# testscreen_4x4.net
KiCad netlist of a schematic drawn in EAGLE
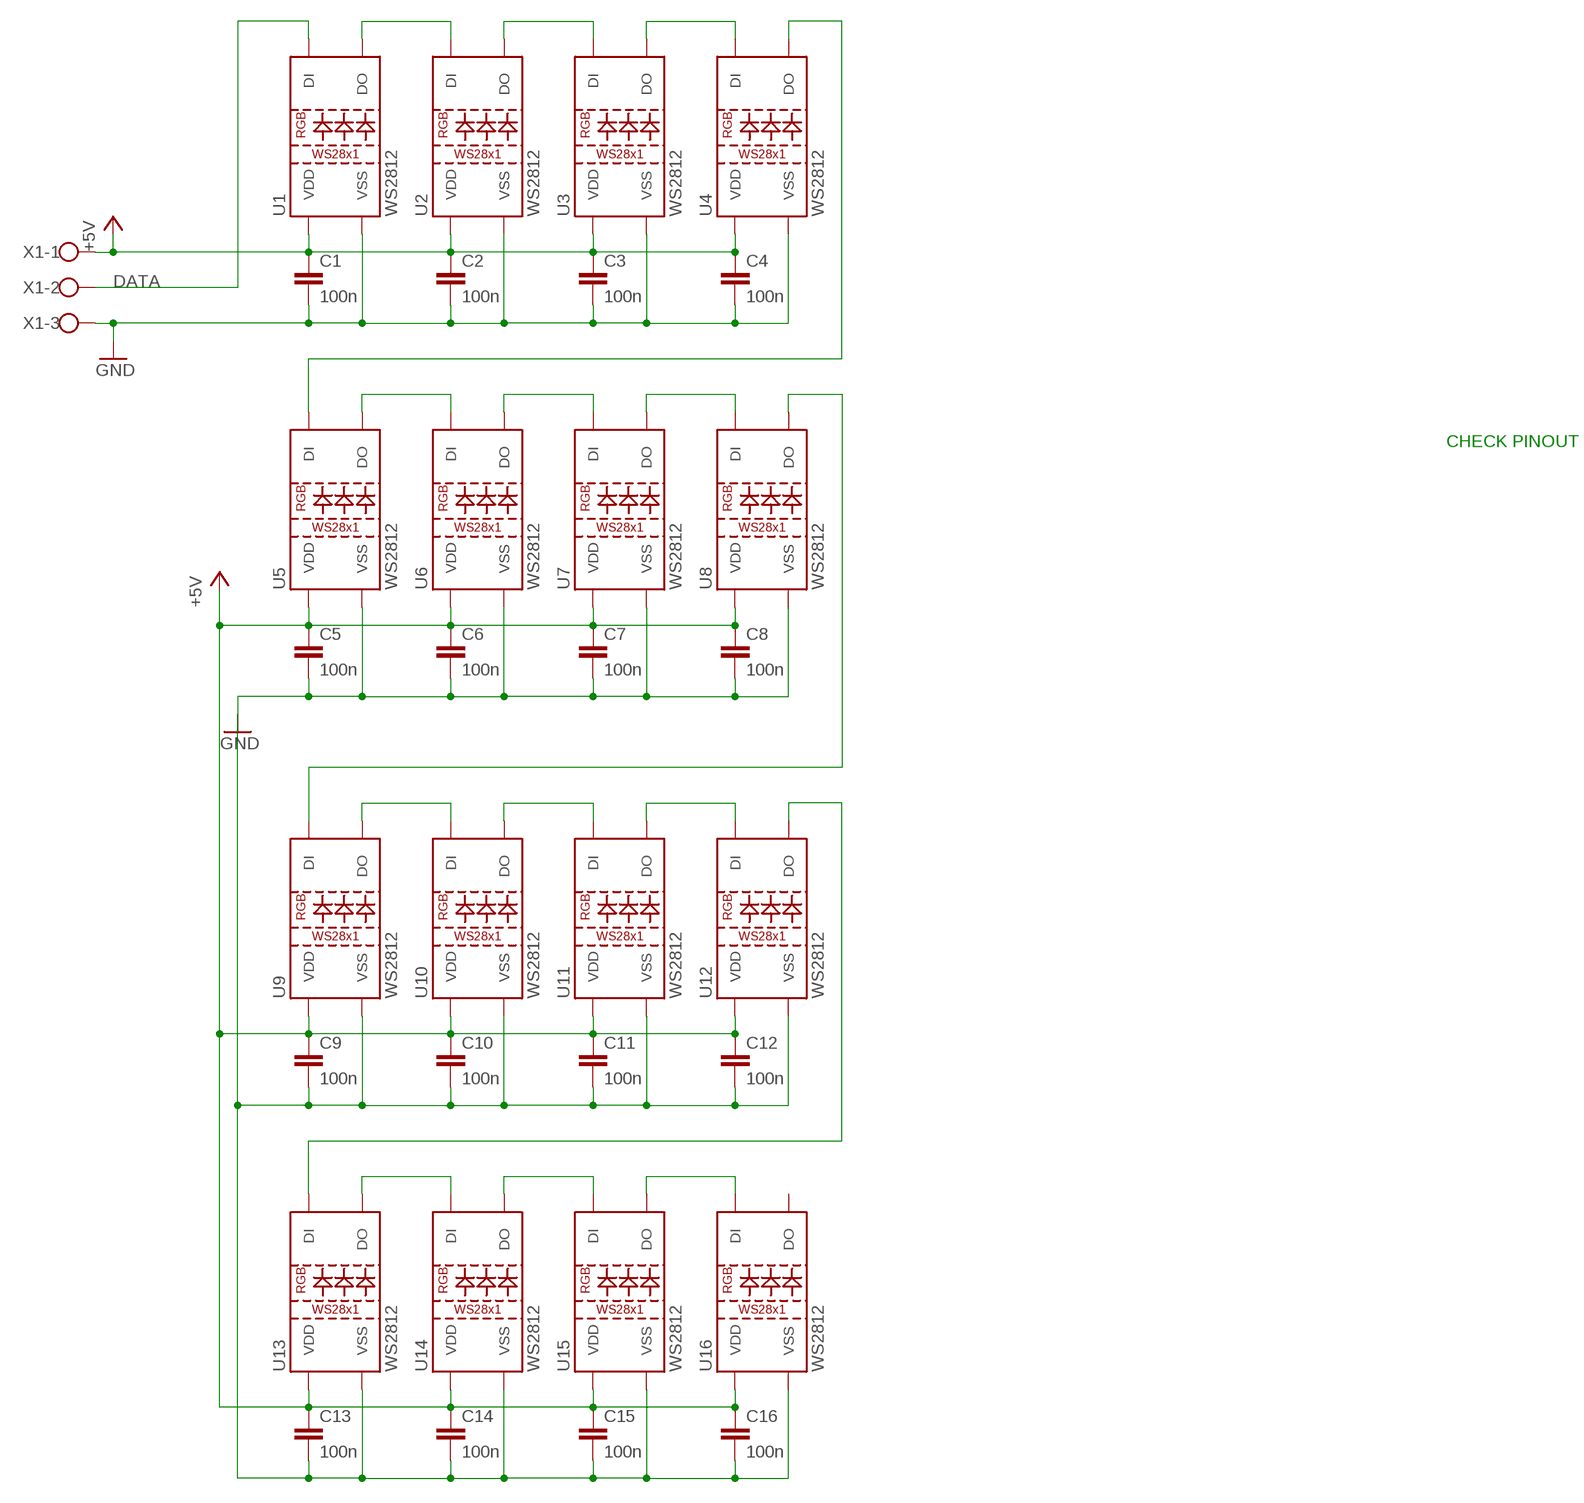
[diagram p0: schematic, sheet 1]

(export (version "E")
  (design (tool "Eeschema 10.0.6"))
  (components
    (comp (ref "C1")
      (value "100n")
      (footprint "eagle-import:C0805")
      (libsource (lib "eagle-import") (part "C-EUC0805"))
    )
    (comp (ref "C2")
      (value "100n")
      (footprint "eagle-import:C0805")
      (libsource (lib "eagle-import") (part "C-EUC0805"))
    )
    (comp (ref "C3")
      (value "100n")
      (footprint "eagle-import:C0805")
      (libsource (lib "eagle-import") (part "C-EUC0805"))
    )
    (comp (ref "C4")
      (value "100n")
      (footprint "eagle-import:C0805")
      (libsource (lib "eagle-import") (part "C-EUC0805"))
    )
    (comp (ref "C5")
      (value "100n")
      (footprint "eagle-import:C0805")
      (libsource (lib "eagle-import") (part "C-EUC0805"))
    )
    (comp (ref "C6")
      (value "100n")
      (footprint "eagle-import:C0805")
      (libsource (lib "eagle-import") (part "C-EUC0805"))
    )
    (comp (ref "C7")
      (value "100n")
      (footprint "eagle-import:C0805")
      (libsource (lib "eagle-import") (part "C-EUC0805"))
    )
    (comp (ref "C8")
      (value "100n")
      (footprint "eagle-import:C0805")
      (libsource (lib "eagle-import") (part "C-EUC0805"))
    )
    (comp (ref "C9")
      (value "100n")
      (footprint "eagle-import:C0805")
      (libsource (lib "eagle-import") (part "C-EUC0805"))
    )
    (comp (ref "C10")
      (value "100n")
      (footprint "eagle-import:C0805")
      (libsource (lib "eagle-import") (part "C-EUC0805"))
    )
    (comp (ref "C11")
      (value "100n")
      (footprint "eagle-import:C0805")
      (libsource (lib "eagle-import") (part "C-EUC0805"))
    )
    (comp (ref "C12")
      (value "100n")
      (footprint "eagle-import:C0805")
      (libsource (lib "eagle-import") (part "C-EUC0805"))
    )
    (comp (ref "C13")
      (value "100n")
      (footprint "eagle-import:C0805")
      (libsource (lib "eagle-import") (part "C-EUC0805"))
    )
    (comp (ref "C14")
      (value "100n")
      (footprint "eagle-import:C0805")
      (libsource (lib "eagle-import") (part "C-EUC0805"))
    )
    (comp (ref "C15")
      (value "100n")
      (footprint "eagle-import:C0805")
      (libsource (lib "eagle-import") (part "C-EUC0805"))
    )
    (comp (ref "C16")
      (value "100n")
      (footprint "eagle-import:C0805")
      (libsource (lib "eagle-import") (part "C-EUC0805"))
    )
    (comp (ref "U1")
      (value "WS2812")
      (footprint "eagle-import:LED-TRICOLOR-5050-IC")
      (libsource (lib "eagle-import") (part "WS2812{dblquote}"))
    )
    (comp (ref "U2")
      (value "WS2812")
      (footprint "eagle-import:LED-TRICOLOR-5050-IC")
      (libsource (lib "eagle-import") (part "WS2812{dblquote}"))
    )
    (comp (ref "U3")
      (value "WS2812")
      (footprint "eagle-import:LED-TRICOLOR-5050-IC")
      (libsource (lib "eagle-import") (part "WS2812{dblquote}"))
    )
    (comp (ref "U4")
      (value "WS2812")
      (footprint "eagle-import:LED-TRICOLOR-5050-IC")
      (libsource (lib "eagle-import") (part "WS2812{dblquote}"))
    )
    (comp (ref "U5")
      (value "WS2812")
      (footprint "eagle-import:LED-TRICOLOR-5050-IC")
      (libsource (lib "eagle-import") (part "WS2812{dblquote}"))
    )
    (comp (ref "U6")
      (value "WS2812")
      (footprint "eagle-import:LED-TRICOLOR-5050-IC")
      (libsource (lib "eagle-import") (part "WS2812{dblquote}"))
    )
    (comp (ref "U7")
      (value "WS2812")
      (footprint "eagle-import:LED-TRICOLOR-5050-IC")
      (libsource (lib "eagle-import") (part "WS2812{dblquote}"))
    )
    (comp (ref "U8")
      (value "WS2812")
      (footprint "eagle-import:LED-TRICOLOR-5050-IC")
      (libsource (lib "eagle-import") (part "WS2812{dblquote}"))
    )
    (comp (ref "U9")
      (value "WS2812")
      (footprint "eagle-import:LED-TRICOLOR-5050-IC")
      (libsource (lib "eagle-import") (part "WS2812{dblquote}"))
    )
    (comp (ref "U10")
      (value "WS2812")
      (footprint "eagle-import:LED-TRICOLOR-5050-IC")
      (libsource (lib "eagle-import") (part "WS2812{dblquote}"))
    )
    (comp (ref "U11")
      (value "WS2812")
      (footprint "eagle-import:LED-TRICOLOR-5050-IC")
      (libsource (lib "eagle-import") (part "WS2812{dblquote}"))
    )
    (comp (ref "U12")
      (value "WS2812")
      (footprint "eagle-import:LED-TRICOLOR-5050-IC")
      (libsource (lib "eagle-import") (part "WS2812{dblquote}"))
    )
    (comp (ref "U13")
      (value "WS2812")
      (footprint "eagle-import:LED-TRICOLOR-5050-IC")
      (libsource (lib "eagle-import") (part "WS2812{dblquote}"))
    )
    (comp (ref "U14")
      (value "WS2812")
      (footprint "eagle-import:LED-TRICOLOR-5050-IC")
      (libsource (lib "eagle-import") (part "WS2812{dblquote}"))
    )
    (comp (ref "U15")
      (value "WS2812")
      (footprint "eagle-import:LED-TRICOLOR-5050-IC")
      (libsource (lib "eagle-import") (part "WS2812{dblquote}"))
    )
    (comp (ref "U16")
      (value "WS2812")
      (footprint "eagle-import:LED-TRICOLOR-5050-IC")
      (libsource (lib "eagle-import") (part "WS2812{dblquote}"))
    )
    (comp (ref "X1")
      (value "W237-103")
      (footprint "eagle-import:W237-103")
      (fields (field (name "MPN") "237-103"))
      (libsource (lib "eagle-import") (part "W237-103"))
    )
  )
  (nets
    (net (code "1") (name "+5V") (class "Default")
      (node (ref "C1") (pin "1") (pinfunction "1_1") (pintype "passive"))
      (node (ref "C10") (pin "1") (pinfunction "1_1") (pintype "passive"))
      (node (ref "C11") (pin "1") (pinfunction "1_1") (pintype "passive"))
      (node (ref "C12") (pin "1") (pinfunction "1_1") (pintype "passive"))
      (node (ref "C13") (pin "1") (pinfunction "1_1") (pintype "passive"))
      (node (ref "C14") (pin "1") (pinfunction "1_1") (pintype "passive"))
      (node (ref "C15") (pin "1") (pinfunction "1_1") (pintype "passive"))
      (node (ref "C16") (pin "1") (pinfunction "1_1") (pintype "passive"))
      (node (ref "C2") (pin "1") (pinfunction "1_1") (pintype "passive"))
      (node (ref "C3") (pin "1") (pinfunction "1_1") (pintype "passive"))
      (node (ref "C4") (pin "1") (pinfunction "1_1") (pintype "passive"))
      (node (ref "C5") (pin "1") (pinfunction "1_1") (pintype "passive"))
      (node (ref "C6") (pin "1") (pinfunction "1_1") (pintype "passive"))
      (node (ref "C7") (pin "1") (pinfunction "1_1") (pintype "passive"))
      (node (ref "C8") (pin "1") (pinfunction "1_1") (pintype "passive"))
      (node (ref "C9") (pin "1") (pinfunction "1_1") (pintype "passive"))
      (node (ref "U1") (pin "3") (pinfunction "VDD_3") (pintype "bidirectional"))
      (node (ref "U1") (pin "5") (pinfunction "VDD_5") (pintype "bidirectional"))
      (node (ref "U10") (pin "3") (pinfunction "VDD_3") (pintype "bidirectional"))
      (node (ref "U10") (pin "5") (pinfunction "VDD_5") (pintype "bidirectional"))
      (node (ref "U11") (pin "3") (pinfunction "VDD_3") (pintype "bidirectional"))
      (node (ref "U11") (pin "5") (pinfunction "VDD_5") (pintype "bidirectional"))
      (node (ref "U12") (pin "3") (pinfunction "VDD_3") (pintype "bidirectional"))
      (node (ref "U12") (pin "5") (pinfunction "VDD_5") (pintype "bidirectional"))
      (node (ref "U13") (pin "3") (pinfunction "VDD_3") (pintype "bidirectional"))
      (node (ref "U13") (pin "5") (pinfunction "VDD_5") (pintype "bidirectional"))
      (node (ref "U14") (pin "3") (pinfunction "VDD_3") (pintype "bidirectional"))
      (node (ref "U14") (pin "5") (pinfunction "VDD_5") (pintype "bidirectional"))
      (node (ref "U15") (pin "3") (pinfunction "VDD_3") (pintype "bidirectional"))
      (node (ref "U15") (pin "5") (pinfunction "VDD_5") (pintype "bidirectional"))
      (node (ref "U16") (pin "3") (pinfunction "VDD_3") (pintype "bidirectional"))
      (node (ref "U16") (pin "5") (pinfunction "VDD_5") (pintype "bidirectional"))
      (node (ref "U2") (pin "3") (pinfunction "VDD_3") (pintype "bidirectional"))
      (node (ref "U2") (pin "5") (pinfunction "VDD_5") (pintype "bidirectional"))
      (node (ref "U3") (pin "3") (pinfunction "VDD_3") (pintype "bidirectional"))
      (node (ref "U3") (pin "5") (pinfunction "VDD_5") (pintype "bidirectional"))
      (node (ref "U4") (pin "3") (pinfunction "VDD_3") (pintype "bidirectional"))
      (node (ref "U4") (pin "5") (pinfunction "VDD_5") (pintype "bidirectional"))
      (node (ref "U5") (pin "3") (pinfunction "VDD_3") (pintype "bidirectional"))
      (node (ref "U5") (pin "5") (pinfunction "VDD_5") (pintype "bidirectional"))
      (node (ref "U6") (pin "3") (pinfunction "VDD_3") (pintype "bidirectional"))
      (node (ref "U6") (pin "5") (pinfunction "VDD_5") (pintype "bidirectional"))
      (node (ref "U7") (pin "3") (pinfunction "VDD_3") (pintype "bidirectional"))
      (node (ref "U7") (pin "5") (pinfunction "VDD_5") (pintype "bidirectional"))
      (node (ref "U8") (pin "3") (pinfunction "VDD_3") (pintype "bidirectional"))
      (node (ref "U8") (pin "5") (pinfunction "VDD_5") (pintype "bidirectional"))
      (node (ref "U9") (pin "3") (pinfunction "VDD_3") (pintype "bidirectional"))
      (node (ref "U9") (pin "5") (pinfunction "VDD_5") (pintype "bidirectional"))
      (node (ref "X1") (pin "1") (pinfunction "KL_1") (pintype "passive"))
    )
    (net (code "2") (name "/DATA") (class "Default")
      (node (ref "U1") (pin "2") (pinfunction "DI_2") (pintype "bidirectional"))
      (node (ref "X1") (pin "2") (pinfunction "KL_2") (pintype "passive"))
    )
    (net (code "3") (name "GND") (class "Default")
      (node (ref "C1") (pin "2") (pinfunction "2_2") (pintype "passive"))
      (node (ref "C10") (pin "2") (pinfunction "2_2") (pintype "passive"))
      (node (ref "C11") (pin "2") (pinfunction "2_2") (pintype "passive"))
      (node (ref "C12") (pin "2") (pinfunction "2_2") (pintype "passive"))
      (node (ref "C13") (pin "2") (pinfunction "2_2") (pintype "passive"))
      (node (ref "C14") (pin "2") (pinfunction "2_2") (pintype "passive"))
      (node (ref "C15") (pin "2") (pinfunction "2_2") (pintype "passive"))
      (node (ref "C16") (pin "2") (pinfunction "2_2") (pintype "passive"))
      (node (ref "C2") (pin "2") (pinfunction "2_2") (pintype "passive"))
      (node (ref "C3") (pin "2") (pinfunction "2_2") (pintype "passive"))
      (node (ref "C4") (pin "2") (pinfunction "2_2") (pintype "passive"))
      (node (ref "C5") (pin "2") (pinfunction "2_2") (pintype "passive"))
      (node (ref "C6") (pin "2") (pinfunction "2_2") (pintype "passive"))
      (node (ref "C7") (pin "2") (pinfunction "2_2") (pintype "passive"))
      (node (ref "C8") (pin "2") (pinfunction "2_2") (pintype "passive"))
      (node (ref "C9") (pin "2") (pinfunction "2_2") (pintype "passive"))
      (node (ref "U1") (pin "6") (pinfunction "VSS_6") (pintype "bidirectional"))
      (node (ref "U10") (pin "6") (pinfunction "VSS_6") (pintype "bidirectional"))
      (node (ref "U11") (pin "6") (pinfunction "VSS_6") (pintype "bidirectional"))
      (node (ref "U12") (pin "6") (pinfunction "VSS_6") (pintype "bidirectional"))
      (node (ref "U13") (pin "6") (pinfunction "VSS_6") (pintype "bidirectional"))
      (node (ref "U14") (pin "6") (pinfunction "VSS_6") (pintype "bidirectional"))
      (node (ref "U15") (pin "6") (pinfunction "VSS_6") (pintype "bidirectional"))
      (node (ref "U16") (pin "6") (pinfunction "VSS_6") (pintype "bidirectional"))
      (node (ref "U2") (pin "6") (pinfunction "VSS_6") (pintype "bidirectional"))
      (node (ref "U3") (pin "6") (pinfunction "VSS_6") (pintype "bidirectional"))
      (node (ref "U4") (pin "6") (pinfunction "VSS_6") (pintype "bidirectional"))
      (node (ref "U5") (pin "6") (pinfunction "VSS_6") (pintype "bidirectional"))
      (node (ref "U6") (pin "6") (pinfunction "VSS_6") (pintype "bidirectional"))
      (node (ref "U7") (pin "6") (pinfunction "VSS_6") (pintype "bidirectional"))
      (node (ref "U8") (pin "6") (pinfunction "VSS_6") (pintype "bidirectional"))
      (node (ref "U9") (pin "6") (pinfunction "VSS_6") (pintype "bidirectional"))
      (node (ref "X1") (pin "3") (pinfunction "KL_3") (pintype "passive"))
    )
    (net (code "4") (name "Net-(U1-DO)") (class "Default")
      (node (ref "U1") (pin "1") (pinfunction "DO_1") (pintype "bidirectional"))
      (node (ref "U2") (pin "2") (pinfunction "DI_2") (pintype "bidirectional"))
    )
    (net (code "5") (name "Net-(U2-DO)") (class "Default")
      (node (ref "U2") (pin "1") (pinfunction "DO_1") (pintype "bidirectional"))
      (node (ref "U3") (pin "2") (pinfunction "DI_2") (pintype "bidirectional"))
    )
    (net (code "6") (name "Net-(U3-DO)") (class "Default")
      (node (ref "U3") (pin "1") (pinfunction "DO_1") (pintype "bidirectional"))
      (node (ref "U4") (pin "2") (pinfunction "DI_2") (pintype "bidirectional"))
    )
    (net (code "7") (name "Net-(U4-DO)") (class "Default")
      (node (ref "U4") (pin "1") (pinfunction "DO_1") (pintype "bidirectional"))
      (node (ref "U5") (pin "2") (pinfunction "DI_2") (pintype "bidirectional"))
    )
    (net (code "8") (name "Net-(U5-DO)") (class "Default")
      (node (ref "U5") (pin "1") (pinfunction "DO_1") (pintype "bidirectional"))
      (node (ref "U6") (pin "2") (pinfunction "DI_2") (pintype "bidirectional"))
    )
    (net (code "9") (name "Net-(U6-DO)") (class "Default")
      (node (ref "U6") (pin "1") (pinfunction "DO_1") (pintype "bidirectional"))
      (node (ref "U7") (pin "2") (pinfunction "DI_2") (pintype "bidirectional"))
    )
    (net (code "10") (name "Net-(U7-DO)") (class "Default")
      (node (ref "U7") (pin "1") (pinfunction "DO_1") (pintype "bidirectional"))
      (node (ref "U8") (pin "2") (pinfunction "DI_2") (pintype "bidirectional"))
    )
    (net (code "11") (name "Net-(U8-DO)") (class "Default")
      (node (ref "U8") (pin "1") (pinfunction "DO_1") (pintype "bidirectional"))
      (node (ref "U9") (pin "2") (pinfunction "DI_2") (pintype "bidirectional"))
    )
    (net (code "12") (name "Net-(U10-DI)") (class "Default")
      (node (ref "U10") (pin "2") (pinfunction "DI_2") (pintype "bidirectional"))
      (node (ref "U9") (pin "1") (pinfunction "DO_1") (pintype "bidirectional"))
    )
    (net (code "13") (name "Net-(U10-DO)") (class "Default")
      (node (ref "U10") (pin "1") (pinfunction "DO_1") (pintype "bidirectional"))
      (node (ref "U11") (pin "2") (pinfunction "DI_2") (pintype "bidirectional"))
    )
    (net (code "14") (name "Net-(U11-DO)") (class "Default")
      (node (ref "U11") (pin "1") (pinfunction "DO_1") (pintype "bidirectional"))
      (node (ref "U12") (pin "2") (pinfunction "DI_2") (pintype "bidirectional"))
    )
    (net (code "15") (name "Net-(U12-DO)") (class "Default")
      (node (ref "U12") (pin "1") (pinfunction "DO_1") (pintype "bidirectional"))
      (node (ref "U13") (pin "2") (pinfunction "DI_2") (pintype "bidirectional"))
    )
    (net (code "16") (name "Net-(U13-DO)") (class "Default")
      (node (ref "U13") (pin "1") (pinfunction "DO_1") (pintype "bidirectional"))
      (node (ref "U14") (pin "2") (pinfunction "DI_2") (pintype "bidirectional"))
    )
    (net (code "17") (name "Net-(U14-DO)") (class "Default")
      (node (ref "U14") (pin "1") (pinfunction "DO_1") (pintype "bidirectional"))
      (node (ref "U15") (pin "2") (pinfunction "DI_2") (pintype "bidirectional"))
    )
    (net (code "18") (name "Net-(U15-DO)") (class "Default")
      (node (ref "U15") (pin "1") (pinfunction "DO_1") (pintype "bidirectional"))
      (node (ref "U16") (pin "2") (pinfunction "DI_2") (pintype "bidirectional"))
    )
    (net (code "19") (name "unconnected-(U16-DO-Pad1)") (class "Default")
      (node (ref "U16") (pin "1") (pinfunction "DO_1") (pintype "bidirectional"))
    )
  )
)
